# PiPowerHat.net
KiCad netlist of a schematic drawn in EAGLE
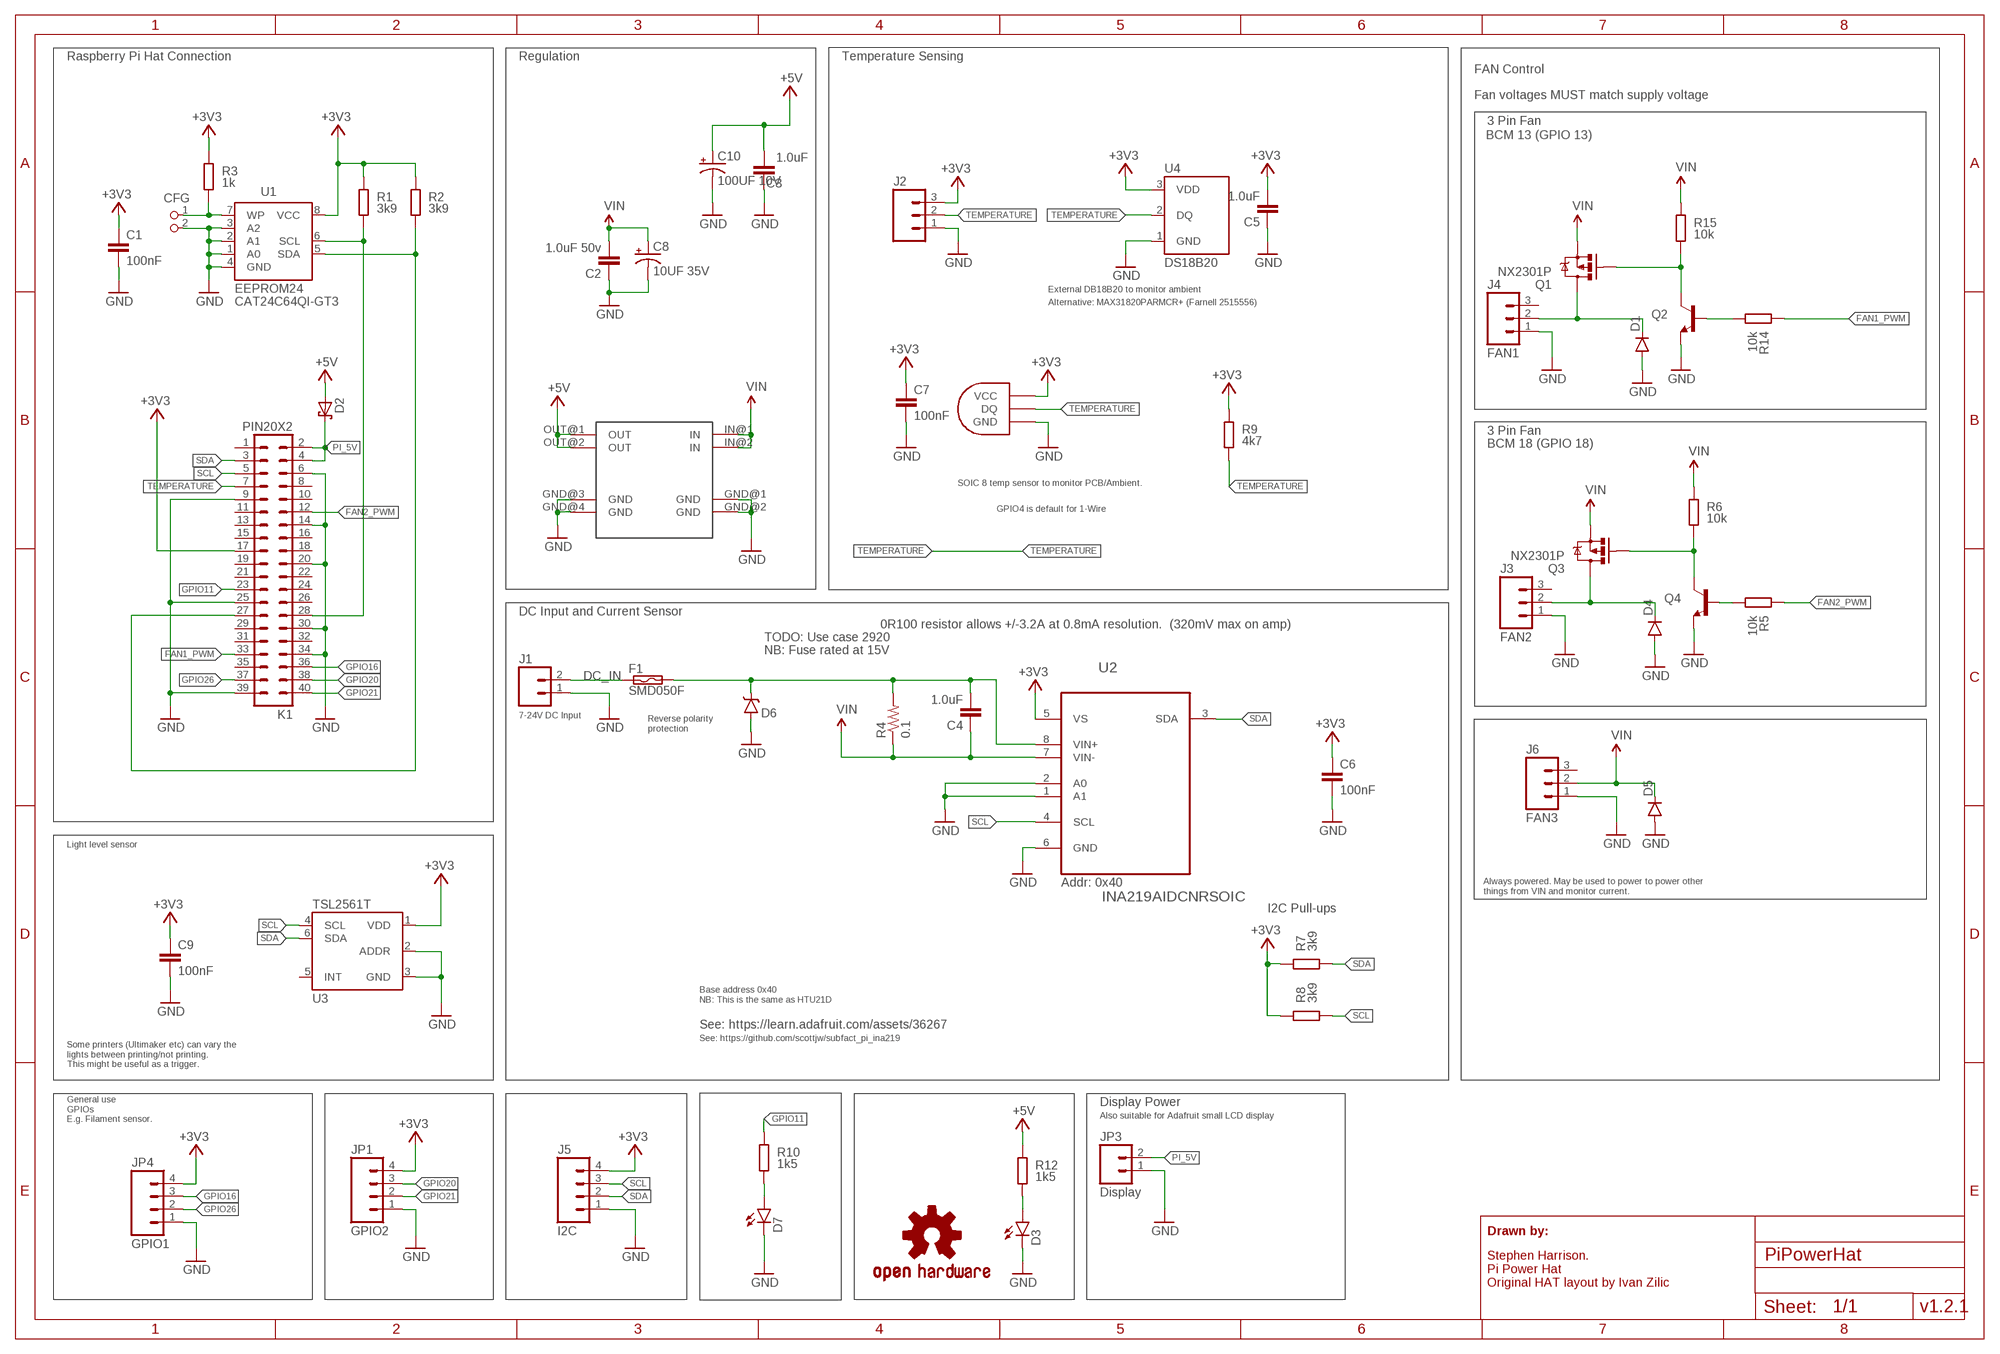
[diagram p0: schematic, sheet 1]

(export (version "E")
  (design (tool "Eeschema 10.0.6"))
  (components
    (comp (ref "C1")
      (value "100nF")
      (footprint "eagle-import:C0805K")
      (libsource (lib "eagle-import") (part "C-EUC0805K"))
    )
    (comp (ref "C2")
      (value "1.0uF 50v")
      (footprint "eagle-import:0805-CAP")
      (libsource (lib "eagle-import") (part "1.0UF-25V-+80/-20(0805){dblquote}"))
    )
    (comp (ref "C3")
      (value "1.0uF")
      (footprint "eagle-import:0805-CAP")
      (libsource (lib "eagle-import") (part "1.0UF-25V-+80/-20(0805){dblquote}"))
    )
    (comp (ref "C4")
      (value "1.0uF")
      (footprint "eagle-import:0805-CAP")
      (libsource (lib "eagle-import") (part "1.0UF-25V-+80/-20(0805){dblquote}"))
    )
    (comp (ref "C5")
      (value "1.0uF")
      (footprint "eagle-import:0805-CAP")
      (libsource (lib "eagle-import") (part "1.0UF-25V-+80/-20(0805){dblquote}"))
    )
    (comp (ref "C6")
      (value "100nF")
      (footprint "eagle-import:C0805K")
      (libsource (lib "eagle-import") (part "C-EUC0805K"))
    )
    (comp (ref "C7")
      (value "100nF")
      (footprint "eagle-import:C0805K")
      (libsource (lib "eagle-import") (part "C-EUC0805K"))
    )
    (comp (ref "C8")
      (value "10UF 35V")
      (footprint "eagle-import:EIA6032-NOM")
      (libsource (lib "eagle-import") (part "10UF-25V-10%(SMT-TANT)"))
    )
    (comp (ref "C9")
      (value "100nF")
      (footprint "eagle-import:C0805K")
      (libsource (lib "eagle-import") (part "C-EUC0805K"))
    )
    (comp (ref "C10")
      (value "100UF 10V")
      (footprint "eagle-import:EIA6032-NOM")
      (libsource (lib "eagle-import") (part "10UF-25V-10%(SMT-TANT)"))
    )
    (comp (ref "CFG")
      (value "PIN2_100")
      (footprint "eagle-import:PIN_W_2")
      (libsource (lib "eagle-import") (part "PIN2_100"))
    )
    (comp (ref "D1")
      (value "DIODESOD123")
      (footprint "eagle-import:SOD-123")
      (libsource (lib "eagle-import") (part "DIODESOD123"))
    )
    (comp (ref "D2")
      (value "MBRS340T3G")
      (footprint "eagle-import:SMC")
      (libsource (lib "eagle-import") (part "SCHOTTKY-DIODESMC"))
    )
    (comp (ref "D3")
      (value "LED1206-BOTTOM")
      (footprint "eagle-import:LED-1206-BOTTOM")
      (libsource (lib "eagle-import") (part "LED1206-BOTTOM"))
    )
    (comp (ref "D4")
      (value "DIODESOD123")
      (footprint "eagle-import:SOD-123")
      (libsource (lib "eagle-import") (part "DIODESOD123"))
    )
    (comp (ref "D5")
      (value "DIODESOD123")
      (footprint "eagle-import:SOD-123")
      (libsource (lib "eagle-import") (part "DIODESOD123"))
    )
    (comp (ref "D6")
      (value "B340A")
      (footprint "eagle-import:SMA-DIODE")
      (libsource (lib "eagle-import") (part "DIODE-SCHOTTKY-B340A"))
    )
    (comp (ref "D7")
      (value "LED1206")
      (footprint "eagle-import:LED-1206")
      (libsource (lib "eagle-import") (part "LED1206"))
    )
    (comp (ref "F1")
      (value "SMD050F")
      (footprint "eagle-import:SMD050F")
      (libsource (lib "eagle-import") (part "SMDF050"))
    )
    (comp (ref "J1")
      (value "M025MM")
      (footprint "eagle-import:SCREWTERMINAL-5MM-2")
      (libsource (lib "eagle-import") (part "M025MM"))
    )
    (comp (ref "J2")
      (value "M03POLAR")
      (footprint "eagle-import:MOLEX-1X3")
      (libsource (lib "eagle-import") (part "M03POLAR"))
    )
    (comp (ref "J3")
      (value "FAN2")
      (footprint "eagle-import:MOLEX-1X3")
      (libsource (lib "eagle-import") (part "M03POLAR"))
    )
    (comp (ref "J4")
      (value "FAN1")
      (footprint "eagle-import:MOLEX-1X3")
      (libsource (lib "eagle-import") (part "M03POLAR"))
    )
    (comp (ref "J5")
      (value "I2C")
      (footprint "eagle-import:MOLEX-1X4")
      (libsource (lib "eagle-import") (part "M04POLAR"))
    )
    (comp (ref "J6")
      (value "FAN3")
      (footprint "eagle-import:MOLEX-1X3")
      (libsource (lib "eagle-import") (part "M03POLAR"))
    )
    (comp (ref "JP1")
      (value "GPIO2")
      (footprint "eagle-import:MOLEX-1X4")
      (libsource (lib "eagle-import") (part "M04POLAR"))
    )
    (comp (ref "JP3")
      (value "Display")
      (footprint "eagle-import:MOLEX-1X2")
      (libsource (lib "eagle-import") (part "M02POLAR"))
    )
    (comp (ref "JP4")
      (value "GPIO1")
      (footprint "eagle-import:MOLEX-1X4")
      (libsource (lib "eagle-import") (part "M04POLAR"))
    )
    (comp (ref "K1")
      (value "PIN20X2")
      (footprint "eagle-import:PIN_20X2")
      (libsource (lib "eagle-import") (part "PIN20X2"))
    )
    (comp (ref "LOGO1")
      (value "OSHW-LOGOM")
      (footprint "eagle-import:OSHW-LOGO-M")
      (libsource (lib "eagle-import") (part "OSHW-LOGOM"))
    )
    (comp (ref "Q1")
      (value "NX2301P")
      (footprint "eagle-import:SOT23-3")
      (libsource (lib "eagle-import") (part "MOSFET-PCHANNEL"))
    )
    (comp (ref "Q2")
      (value "TRANSISTOR_NPNSOT23-3")
      (footprint "eagle-import:SOT23-3")
      (libsource (lib "eagle-import") (part "TRANSISTOR_NPNSOT23-3"))
    )
    (comp (ref "Q3")
      (value "NX2301P")
      (footprint "eagle-import:SOT23-3")
      (libsource (lib "eagle-import") (part "MOSFET-PCHANNEL"))
    )
    (comp (ref "Q4")
      (value "TRANSISTOR_NPNSOT23-3")
      (footprint "eagle-import:SOT23-3")
      (libsource (lib "eagle-import") (part "TRANSISTOR_NPNSOT23-3"))
    )
    (comp (ref "R1")
      (value "3k9")
      (footprint "eagle-import:M0805")
      (fields (field (name "TOLERANCE") "5%"))
      (libsource (lib "eagle-import") (part "R-EU_M0805"))
    )
    (comp (ref "R2")
      (value "3k9")
      (footprint "eagle-import:M0805")
      (fields (field (name "TOLERANCE") "5%"))
      (libsource (lib "eagle-import") (part "R-EU_M0805"))
    )
    (comp (ref "R3")
      (value "1k")
      (footprint "eagle-import:M0805")
      (fields (field (name "TOLERANCE") "5%"))
      (libsource (lib "eagle-import") (part "R-EU_M0805"))
    )
    (comp (ref "R4")
      (value "0.1")
      (footprint "eagle-import:2512")
      (libsource (lib "eagle-import") (part "0.001OHM-3W-1%(2512)3W/1%"))
    )
    (comp (ref "R5")
      (value "10k")
      (footprint "eagle-import:M0805")
      (fields (field (name "TOLERANCE") "5%"))
      (libsource (lib "eagle-import") (part "R-EU_M0805"))
    )
    (comp (ref "R6")
      (value "10k")
      (footprint "eagle-import:M0805")
      (fields (field (name "TOLERANCE") "5%"))
      (libsource (lib "eagle-import") (part "R-EU_M0805"))
    )
    (comp (ref "R7")
      (value "3k9")
      (footprint "eagle-import:M0805")
      (fields (field (name "TOLERANCE") "5%"))
      (libsource (lib "eagle-import") (part "R-EU_M0805"))
    )
    (comp (ref "R8")
      (value "3k9")
      (footprint "eagle-import:M0805")
      (fields (field (name "TOLERANCE") "5%"))
      (libsource (lib "eagle-import") (part "R-EU_M0805"))
    )
    (comp (ref "R9")
      (value "4k7")
      (footprint "eagle-import:M0805")
      (fields (field (name "TOLERANCE") "5%"))
      (libsource (lib "eagle-import") (part "R-EU_M0805"))
    )
    (comp (ref "R10")
      (value "1k5")
      (footprint "eagle-import:M0805")
      (fields (field (name "TOLERANCE") "5%"))
      (libsource (lib "eagle-import") (part "R-EU_M0805"))
    )
    (comp (ref "R12")
      (value "1k5")
      (footprint "eagle-import:M0805")
      (fields (field (name "TOLERANCE") "5%"))
      (libsource (lib "eagle-import") (part "R-EU_M0805"))
    )
    (comp (ref "R14")
      (value "10k")
      (footprint "eagle-import:M0805")
      (fields (field (name "TOLERANCE") "5%"))
      (libsource (lib "eagle-import") (part "R-EU_M0805"))
    )
    (comp (ref "R15")
      (value "10k")
      (footprint "eagle-import:M0805")
      (fields (field (name "TOLERANCE") "5%"))
      (libsource (lib "eagle-import") (part "R-EU_M0805"))
    )
    (comp (ref "RG1")
      (value "MINI-BUCK-MODULE-3A")
      (footprint "eagle-import:MINI-BUCK-MODULE-3A")
      (libsource (lib "eagle-import") (part "MINI-BUCK-MODULE-3A"))
    )
    (comp (ref "U1")
      (value "EEPROM24")
      (footprint "eagle-import:SOIC8")
      (libsource (lib "eagle-import") (part "EEPROM24"))
    )
    (comp (ref "U2")
      (value "INA219AIDCNRSOIC")
      (footprint "eagle-import:SO08")
      (libsource (lib "eagle-import") (part "INA219AIDCNRSOIC"))
    )
    (comp (ref "U3")
      (value "TSL2561T")
      (footprint "eagle-import:TMB-6")
      (libsource (lib "eagle-import") (part "TSL2561T"))
    )
    (comp (ref "U4")
      (value "DS18B20")
      (footprint "eagle-import:TO-92-AMMO")
      (libsource (lib "eagle-import") (part "DS18B20"))
    )
    (comp (ref "U5")
      (value "DS1820SOIC")
      (footprint "eagle-import:DS18B20_SOIC")
      (libsource (lib "eagle-import") (part "DS1820SOIC"))
    )
  )
  (nets
    (net (code "1") (name "+3V3") (class "Default")
      (node (ref "C1") (pin "1") (pinfunction "1_1") (pintype "passive"))
      (node (ref "C5") (pin "2") (pinfunction "2_2") (pintype "passive"))
      (node (ref "C6") (pin "1") (pinfunction "1_1") (pintype "passive"))
      (node (ref "C7") (pin "1") (pinfunction "1_1") (pintype "passive"))
      (node (ref "C9") (pin "1") (pinfunction "1_1") (pintype "passive"))
      (node (ref "J2") (pin "3") (pinfunction "3_3") (pintype "passive"))
      (node (ref "J5") (pin "4") (pinfunction "4_4") (pintype "passive"))
      (node (ref "JP1") (pin "4") (pinfunction "4_4") (pintype "passive"))
      (node (ref "JP4") (pin "4") (pinfunction "4_4") (pintype "passive"))
      (node (ref "K1") (pin "17") (pinfunction "17_17") (pintype "passive"))
      (node (ref "R1") (pin "2") (pinfunction "2_2") (pintype "passive"))
      (node (ref "R2") (pin "2") (pinfunction "2_2") (pintype "passive"))
      (node (ref "R3") (pin "2") (pinfunction "2_2") (pintype "passive"))
      (node (ref "R7") (pin "2") (pinfunction "2_2") (pintype "passive"))
      (node (ref "R8") (pin "2") (pinfunction "2_2") (pintype "passive"))
      (node (ref "R9") (pin "2") (pinfunction "2_2") (pintype "passive"))
      (node (ref "U1") (pin "8") (pinfunction "VCC_8") (pintype "power_in"))
      (node (ref "U2") (pin "5") (pinfunction "VS_5") (pintype "power_in"))
      (node (ref "U3") (pin "1") (pinfunction "VDD_1") (pintype "power_in"))
      (node (ref "U4") (pin "3") (pinfunction "VDD_3") (pintype "power_in"))
      (node (ref "U5") (pin "VCC") (pinfunction "VCC_VCC") (pintype "power_in"))
    )
    (net (code "2") (name "+5V") (class "Default")
      (node (ref "C10") (pin "A") (pinfunction "+_A") (pintype "passive"))
      (node (ref "C3") (pin "2") (pinfunction "2_2") (pintype "passive"))
      (node (ref "D2") (pin "A") (pinfunction "A_A") (pintype "passive"))
      (node (ref "R12") (pin "2") (pinfunction "2_2") (pintype "passive"))
      (node (ref "RG1") (pin "OUT@1") (pinfunction "OUT_OUT@1") (pintype "bidirectional"))
      (node (ref "RG1") (pin "OUT@2") (pinfunction "OUT_OUT@2") (pintype "bidirectional"))
    )
    (net (code "3") (name "/DC_IN") (class "Default")
      (node (ref "F1") (pin "1") (pinfunction "1_1") (pintype "passive"))
      (node (ref "J1") (pin "2") (pinfunction "2_2") (pintype "passive"))
    )
    (net (code "4") (name "FAN1_PWM") (class "Default")
      (node (ref "K1") (pin "33") (pinfunction "33_33") (pintype "passive"))
      (node (ref "R14") (pin "2") (pinfunction "2_2") (pintype "passive"))
    )
    (net (code "5") (name "FAN2_PWM") (class "Default")
      (node (ref "K1") (pin "12") (pinfunction "12_12") (pintype "passive"))
      (node (ref "R5") (pin "2") (pinfunction "2_2") (pintype "passive"))
    )
    (net (code "6") (name "GND") (class "Default")
      (node (ref "C1") (pin "2") (pinfunction "2_2") (pintype "passive"))
      (node (ref "C10") (pin "C") (pinfunction "-_C") (pintype "passive"))
      (node (ref "C2") (pin "1") (pinfunction "1_1") (pintype "passive"))
      (node (ref "C3") (pin "1") (pinfunction "1_1") (pintype "passive"))
      (node (ref "C5") (pin "1") (pinfunction "1_1") (pintype "passive"))
      (node (ref "C6") (pin "2") (pinfunction "2_2") (pintype "passive"))
      (node (ref "C7") (pin "2") (pinfunction "2_2") (pintype "passive"))
      (node (ref "C8") (pin "C") (pinfunction "-_C") (pintype "passive"))
      (node (ref "C9") (pin "2") (pinfunction "2_2") (pintype "passive"))
      (node (ref "CFG") (pin "2") (pinfunction "2_2") (pintype "passive"))
      (node (ref "D1") (pin "A") (pinfunction "A_A") (pintype "passive"))
      (node (ref "D3") (pin "C") (pinfunction "C_C") (pintype "passive"))
      (node (ref "D4") (pin "A") (pinfunction "A_A") (pintype "passive"))
      (node (ref "D5") (pin "A") (pinfunction "A_A") (pintype "passive"))
      (node (ref "D6") (pin "A") (pinfunction "A_A") (pintype "passive"))
      (node (ref "D7") (pin "C") (pinfunction "C_C") (pintype "passive"))
      (node (ref "J1") (pin "1") (pinfunction "1_1") (pintype "passive"))
      (node (ref "J2") (pin "1") (pinfunction "1_1") (pintype "passive"))
      (node (ref "J3") (pin "1") (pinfunction "1_1") (pintype "passive"))
      (node (ref "J4") (pin "1") (pinfunction "1_1") (pintype "passive"))
      (node (ref "J5") (pin "1") (pinfunction "1_1") (pintype "passive"))
      (node (ref "J6") (pin "1") (pinfunction "1_1") (pintype "passive"))
      (node (ref "JP1") (pin "1") (pinfunction "1_1") (pintype "passive"))
      (node (ref "JP3") (pin "1") (pinfunction "1_1") (pintype "passive"))
      (node (ref "JP4") (pin "1") (pinfunction "1_1") (pintype "passive"))
      (node (ref "K1") (pin "14") (pinfunction "14_14") (pintype "passive"))
      (node (ref "K1") (pin "20") (pinfunction "20_20") (pintype "passive"))
      (node (ref "K1") (pin "25") (pinfunction "25_25") (pintype "passive"))
      (node (ref "K1") (pin "30") (pinfunction "30_30") (pintype "passive"))
      (node (ref "K1") (pin "34") (pinfunction "34_34") (pintype "passive"))
      (node (ref "K1") (pin "39") (pinfunction "39_39") (pintype "passive"))
      (node (ref "K1") (pin "6") (pinfunction "6_6") (pintype "passive"))
      (node (ref "K1") (pin "9") (pinfunction "9_9") (pintype "passive"))
      (node (ref "Q2") (pin "2") (pinfunction "E_2") (pintype "passive"))
      (node (ref "Q4") (pin "2") (pinfunction "E_2") (pintype "passive"))
      (node (ref "RG1") (pin "GND@1") (pinfunction "GND_GND@1") (pintype "bidirectional"))
      (node (ref "RG1") (pin "GND@2") (pinfunction "GND_GND@2") (pintype "bidirectional"))
      (node (ref "RG1") (pin "GND@3") (pinfunction "GND_GND@3") (pintype "bidirectional"))
      (node (ref "RG1") (pin "GND@4") (pinfunction "GND_GND@4") (pintype "bidirectional"))
      (node (ref "U1") (pin "1") (pinfunction "A0_1") (pintype "input"))
      (node (ref "U1") (pin "2") (pinfunction "A1_2") (pintype "input"))
      (node (ref "U1") (pin "3") (pinfunction "A2_3") (pintype "input"))
      (node (ref "U1") (pin "4") (pinfunction "GND_4") (pintype "power_in"))
      (node (ref "U2") (pin "1") (pinfunction "A1_1") (pintype "input"))
      (node (ref "U2") (pin "2") (pinfunction "A0_2") (pintype "input"))
      (node (ref "U2") (pin "6") (pinfunction "GND_6") (pintype "passive"))
      (node (ref "U3") (pin "2") (pinfunction "ADDR_2") (pintype "input"))
      (node (ref "U3") (pin "3") (pinfunction "GND_3") (pintype "power_in"))
      (node (ref "U4") (pin "1") (pinfunction "GND_1") (pintype "power_in"))
      (node (ref "U5") (pin "GND") (pinfunction "GND_GND") (pintype "power_in"))
    )
    (net (code "7") (name "GPIO11") (class "Default")
      (node (ref "K1") (pin "23") (pinfunction "23_23") (pintype "passive"))
      (node (ref "R10") (pin "2") (pinfunction "2_2") (pintype "passive"))
    )
    (net (code "8") (name "GPIO16") (class "Default")
      (node (ref "JP4") (pin "3") (pinfunction "3_3") (pintype "passive"))
      (node (ref "K1") (pin "36") (pinfunction "36_36") (pintype "passive"))
    )
    (net (code "9") (name "GPIO20") (class "Default")
      (node (ref "JP1") (pin "3") (pinfunction "3_3") (pintype "passive"))
      (node (ref "K1") (pin "38") (pinfunction "38_38") (pintype "passive"))
    )
    (net (code "10") (name "GPIO21") (class "Default")
      (node (ref "JP1") (pin "2") (pinfunction "2_2") (pintype "passive"))
      (node (ref "K1") (pin "40") (pinfunction "40_40") (pintype "passive"))
    )
    (net (code "11") (name "GPIO26") (class "Default")
      (node (ref "JP4") (pin "2") (pinfunction "2_2") (pintype "passive"))
      (node (ref "K1") (pin "37") (pinfunction "37_37") (pintype "passive"))
    )
    (net (code "12") (name "Net-(D3-PadA)") (class "Default")
      (node (ref "D3") (pin "A") (pinfunction "A_A") (pintype "passive"))
      (node (ref "R12") (pin "1") (pinfunction "1_1") (pintype "passive"))
    )
    (net (code "13") (name "Net-(D7-PadA)") (class "Default")
      (node (ref "D7") (pin "A") (pinfunction "A_A") (pintype "passive"))
      (node (ref "R10") (pin "1") (pinfunction "1_1") (pintype "passive"))
    )
    (net (code "14") (name "Net-(Q1-D)") (class "Default")
      (node (ref "D1") (pin "C") (pinfunction "C_C") (pintype "passive"))
      (node (ref "J4") (pin "2") (pinfunction "2_2") (pintype "passive"))
      (node (ref "Q1") (pin "3") (pinfunction "D_3") (pintype "passive"))
    )
    (net (code "15") (name "Net-(Q1-G)") (class "Default")
      (node (ref "Q1") (pin "1") (pinfunction "G_1") (pintype "passive"))
      (node (ref "Q2") (pin "3") (pinfunction "C_3") (pintype "passive"))
      (node (ref "R15") (pin "1") (pinfunction "1_1") (pintype "passive"))
    )
    (net (code "16") (name "Net-(Q2-B)") (class "Default")
      (node (ref "Q2") (pin "1") (pinfunction "B_1") (pintype "passive"))
      (node (ref "R14") (pin "1") (pinfunction "1_1") (pintype "passive"))
    )
    (net (code "17") (name "Net-(Q3-D)") (class "Default")
      (node (ref "D4") (pin "C") (pinfunction "C_C") (pintype "passive"))
      (node (ref "J3") (pin "2") (pinfunction "2_2") (pintype "passive"))
      (node (ref "Q3") (pin "3") (pinfunction "D_3") (pintype "passive"))
    )
    (net (code "18") (name "Net-(Q3-G)") (class "Default")
      (node (ref "Q3") (pin "1") (pinfunction "G_1") (pintype "passive"))
      (node (ref "Q4") (pin "3") (pinfunction "C_3") (pintype "passive"))
      (node (ref "R6") (pin "1") (pinfunction "1_1") (pintype "passive"))
    )
    (net (code "19") (name "Net-(Q4-B)") (class "Default")
      (node (ref "Q4") (pin "1") (pinfunction "B_1") (pintype "passive"))
      (node (ref "R5") (pin "1") (pinfunction "1_1") (pintype "passive"))
    )
    (net (code "20") (name "Net-(U1-SCL)") (class "Default")
      (node (ref "K1") (pin "28") (pinfunction "28_28") (pintype "passive"))
      (node (ref "R1") (pin "1") (pinfunction "1_1") (pintype "passive"))
      (node (ref "U1") (pin "6") (pinfunction "SCL_6") (pintype "input"))
    )
    (net (code "21") (name "Net-(U1-SDA)") (class "Default")
      (node (ref "K1") (pin "27") (pinfunction "27_27") (pintype "passive"))
      (node (ref "R2") (pin "1") (pinfunction "1_1") (pintype "passive"))
      (node (ref "U1") (pin "5") (pinfunction "SDA_5") (pintype "bidirectional"))
    )
    (net (code "22") (name "Net-(U1-WP)") (class "Default")
      (node (ref "CFG") (pin "1") (pinfunction "1_1") (pintype "passive"))
      (node (ref "R3") (pin "1") (pinfunction "1_1") (pintype "passive"))
      (node (ref "U1") (pin "7") (pinfunction "WP_7") (pintype "input"))
    )
    (net (code "23") (name "Net-(U2-VIN+)") (class "Default")
      (node (ref "C4") (pin "2") (pinfunction "2_2") (pintype "passive"))
      (node (ref "D6") (pin "C") (pinfunction "C_C") (pintype "passive"))
      (node (ref "F1") (pin "2") (pinfunction "2_2") (pintype "passive"))
      (node (ref "R4") (pin "2") (pinfunction "2_2") (pintype "passive"))
      (node (ref "U2") (pin "8") (pinfunction "VIN+_8") (pintype "input"))
    )
    (net (code "24") (name "PI_5V") (class "Default")
      (node (ref "D2") (pin "C") (pinfunction "C_C") (pintype "passive"))
      (node (ref "JP3") (pin "2") (pinfunction "2_2") (pintype "passive"))
      (node (ref "K1") (pin "2") (pinfunction "2_2") (pintype "passive"))
      (node (ref "K1") (pin "4") (pinfunction "4_4") (pintype "passive"))
    )
    (net (code "25") (name "SCL") (class "Default")
      (node (ref "J5") (pin "3") (pinfunction "3_3") (pintype "passive"))
      (node (ref "K1") (pin "5") (pinfunction "5_5") (pintype "passive"))
      (node (ref "R8") (pin "1") (pinfunction "1_1") (pintype "passive"))
      (node (ref "U2") (pin "4") (pinfunction "SCL_4") (pintype "input"))
      (node (ref "U3") (pin "4") (pinfunction "SCL_4") (pintype "input"))
    )
    (net (code "26") (name "SDA") (class "Default")
      (node (ref "J5") (pin "2") (pinfunction "2_2") (pintype "passive"))
      (node (ref "K1") (pin "3") (pinfunction "3_3") (pintype "passive"))
      (node (ref "R7") (pin "1") (pinfunction "1_1") (pintype "passive"))
      (node (ref "U2") (pin "3") (pinfunction "SDA_3") (pintype "bidirectional"))
      (node (ref "U3") (pin "6") (pinfunction "SDA_6") (pintype "bidirectional"))
    )
    (net (code "27") (name "TEMPERATURE") (class "Default")
      (node (ref "J2") (pin "2") (pinfunction "2_2") (pintype "passive"))
      (node (ref "K1") (pin "7") (pinfunction "7_7") (pintype "passive"))
      (node (ref "R9") (pin "1") (pinfunction "1_1") (pintype "passive"))
      (node (ref "U4") (pin "2") (pinfunction "DQ_2") (pintype "bidirectional"))
      (node (ref "U5") (pin "DQ") (pinfunction "DQ_DQ") (pintype "bidirectional"))
    )
    (net (code "28") (name "VIN") (class "Default")
      (node (ref "C2") (pin "2") (pinfunction "2_2") (pintype "passive"))
      (node (ref "C4") (pin "1") (pinfunction "1_1") (pintype "passive"))
      (node (ref "C8") (pin "A") (pinfunction "+_A") (pintype "passive"))
      (node (ref "D5") (pin "C") (pinfunction "C_C") (pintype "passive"))
      (node (ref "J6") (pin "2") (pinfunction "2_2") (pintype "passive"))
      (node (ref "Q1") (pin "2") (pinfunction "S_2") (pintype "passive"))
      (node (ref "Q3") (pin "2") (pinfunction "S_2") (pintype "passive"))
      (node (ref "R15") (pin "2") (pinfunction "2_2") (pintype "passive"))
      (node (ref "R4") (pin "1") (pinfunction "1_1") (pintype "passive"))
      (node (ref "R6") (pin "2") (pinfunction "2_2") (pintype "passive"))
      (node (ref "RG1") (pin "IN@1") (pinfunction "IN_IN@1") (pintype "bidirectional"))
      (node (ref "RG1") (pin "IN@2") (pinfunction "IN_IN@2") (pintype "bidirectional"))
      (node (ref "U2") (pin "7") (pinfunction "VIN-_7") (pintype "input"))
    )
    (net (code "29") (name "unconnected-(J3-Pad3)") (class "Default")
      (node (ref "J3") (pin "3") (pinfunction "3_3") (pintype "passive"))
    )
    (net (code "30") (name "unconnected-(J4-Pad3)") (class "Default")
      (node (ref "J4") (pin "3") (pinfunction "3_3") (pintype "passive"))
    )
    (net (code "31") (name "unconnected-(J6-Pad3)") (class "Default")
      (node (ref "J6") (pin "3") (pinfunction "3_3") (pintype "passive"))
    )
    (net (code "32") (name "unconnected-(K1-Pad1)") (class "Default")
      (node (ref "K1") (pin "1") (pinfunction "1_1") (pintype "passive"))
    )
    (net (code "33") (name "unconnected-(K1-Pad8)") (class "Default")
      (node (ref "K1") (pin "8") (pinfunction "8_8") (pintype "passive"))
    )
    (net (code "34") (name "unconnected-(K1-Pad10)") (class "Default")
      (node (ref "K1") (pin "10") (pinfunction "10_10") (pintype "passive"))
    )
    (net (code "35") (name "unconnected-(K1-Pad11)") (class "Default")
      (node (ref "K1") (pin "11") (pinfunction "11_11") (pintype "passive"))
    )
    (net (code "36") (name "unconnected-(K1-Pad13)") (class "Default")
      (node (ref "K1") (pin "13") (pinfunction "13_13") (pintype "passive"))
    )
    (net (code "37") (name "unconnected-(K1-Pad15)") (class "Default")
      (node (ref "K1") (pin "15") (pinfunction "15_15") (pintype "passive"))
    )
    (net (code "38") (name "unconnected-(K1-Pad16)") (class "Default")
      (node (ref "K1") (pin "16") (pinfunction "16_16") (pintype "passive"))
    )
    (net (code "39") (name "unconnected-(K1-Pad18)") (class "Default")
      (node (ref "K1") (pin "18") (pinfunction "18_18") (pintype "passive"))
    )
    (net (code "40") (name "unconnected-(K1-Pad19)") (class "Default")
      (node (ref "K1") (pin "19") (pinfunction "19_19") (pintype "passive"))
    )
    (net (code "41") (name "unconnected-(K1-Pad21)") (class "Default")
      (node (ref "K1") (pin "21") (pinfunction "21_21") (pintype "passive"))
    )
    (net (code "42") (name "unconnected-(K1-Pad22)") (class "Default")
      (node (ref "K1") (pin "22") (pinfunction "22_22") (pintype "passive"))
    )
    (net (code "43") (name "unconnected-(K1-Pad24)") (class "Default")
      (node (ref "K1") (pin "24") (pinfunction "24_24") (pintype "passive"))
    )
    (net (code "44") (name "unconnected-(K1-Pad26)") (class "Default")
      (node (ref "K1") (pin "26") (pinfunction "26_26") (pintype "passive"))
    )
    (net (code "45") (name "unconnected-(K1-Pad29)") (class "Default")
      (node (ref "K1") (pin "29") (pinfunction "29_29") (pintype "passive"))
    )
    (net (code "46") (name "unconnected-(K1-Pad31)") (class "Default")
      (node (ref "K1") (pin "31") (pinfunction "31_31") (pintype "passive"))
    )
    (net (code "47") (name "unconnected-(K1-Pad32)") (class "Default")
      (node (ref "K1") (pin "32") (pinfunction "32_32") (pintype "passive"))
    )
    (net (code "48") (name "unconnected-(K1-Pad35)") (class "Default")
      (node (ref "K1") (pin "35") (pinfunction "35_35") (pintype "passive"))
    )
    (net (code "49") (name "unconnected-(U3-INT-Pad5)") (class "Default")
      (node (ref "U3") (pin "5") (pinfunction "INT_5") (pintype "output"))
    )
  )
)
